# 1-Schematic_PIC18F_Breakout.net
KiCad netlist of a schematic drawn in EasyEDA
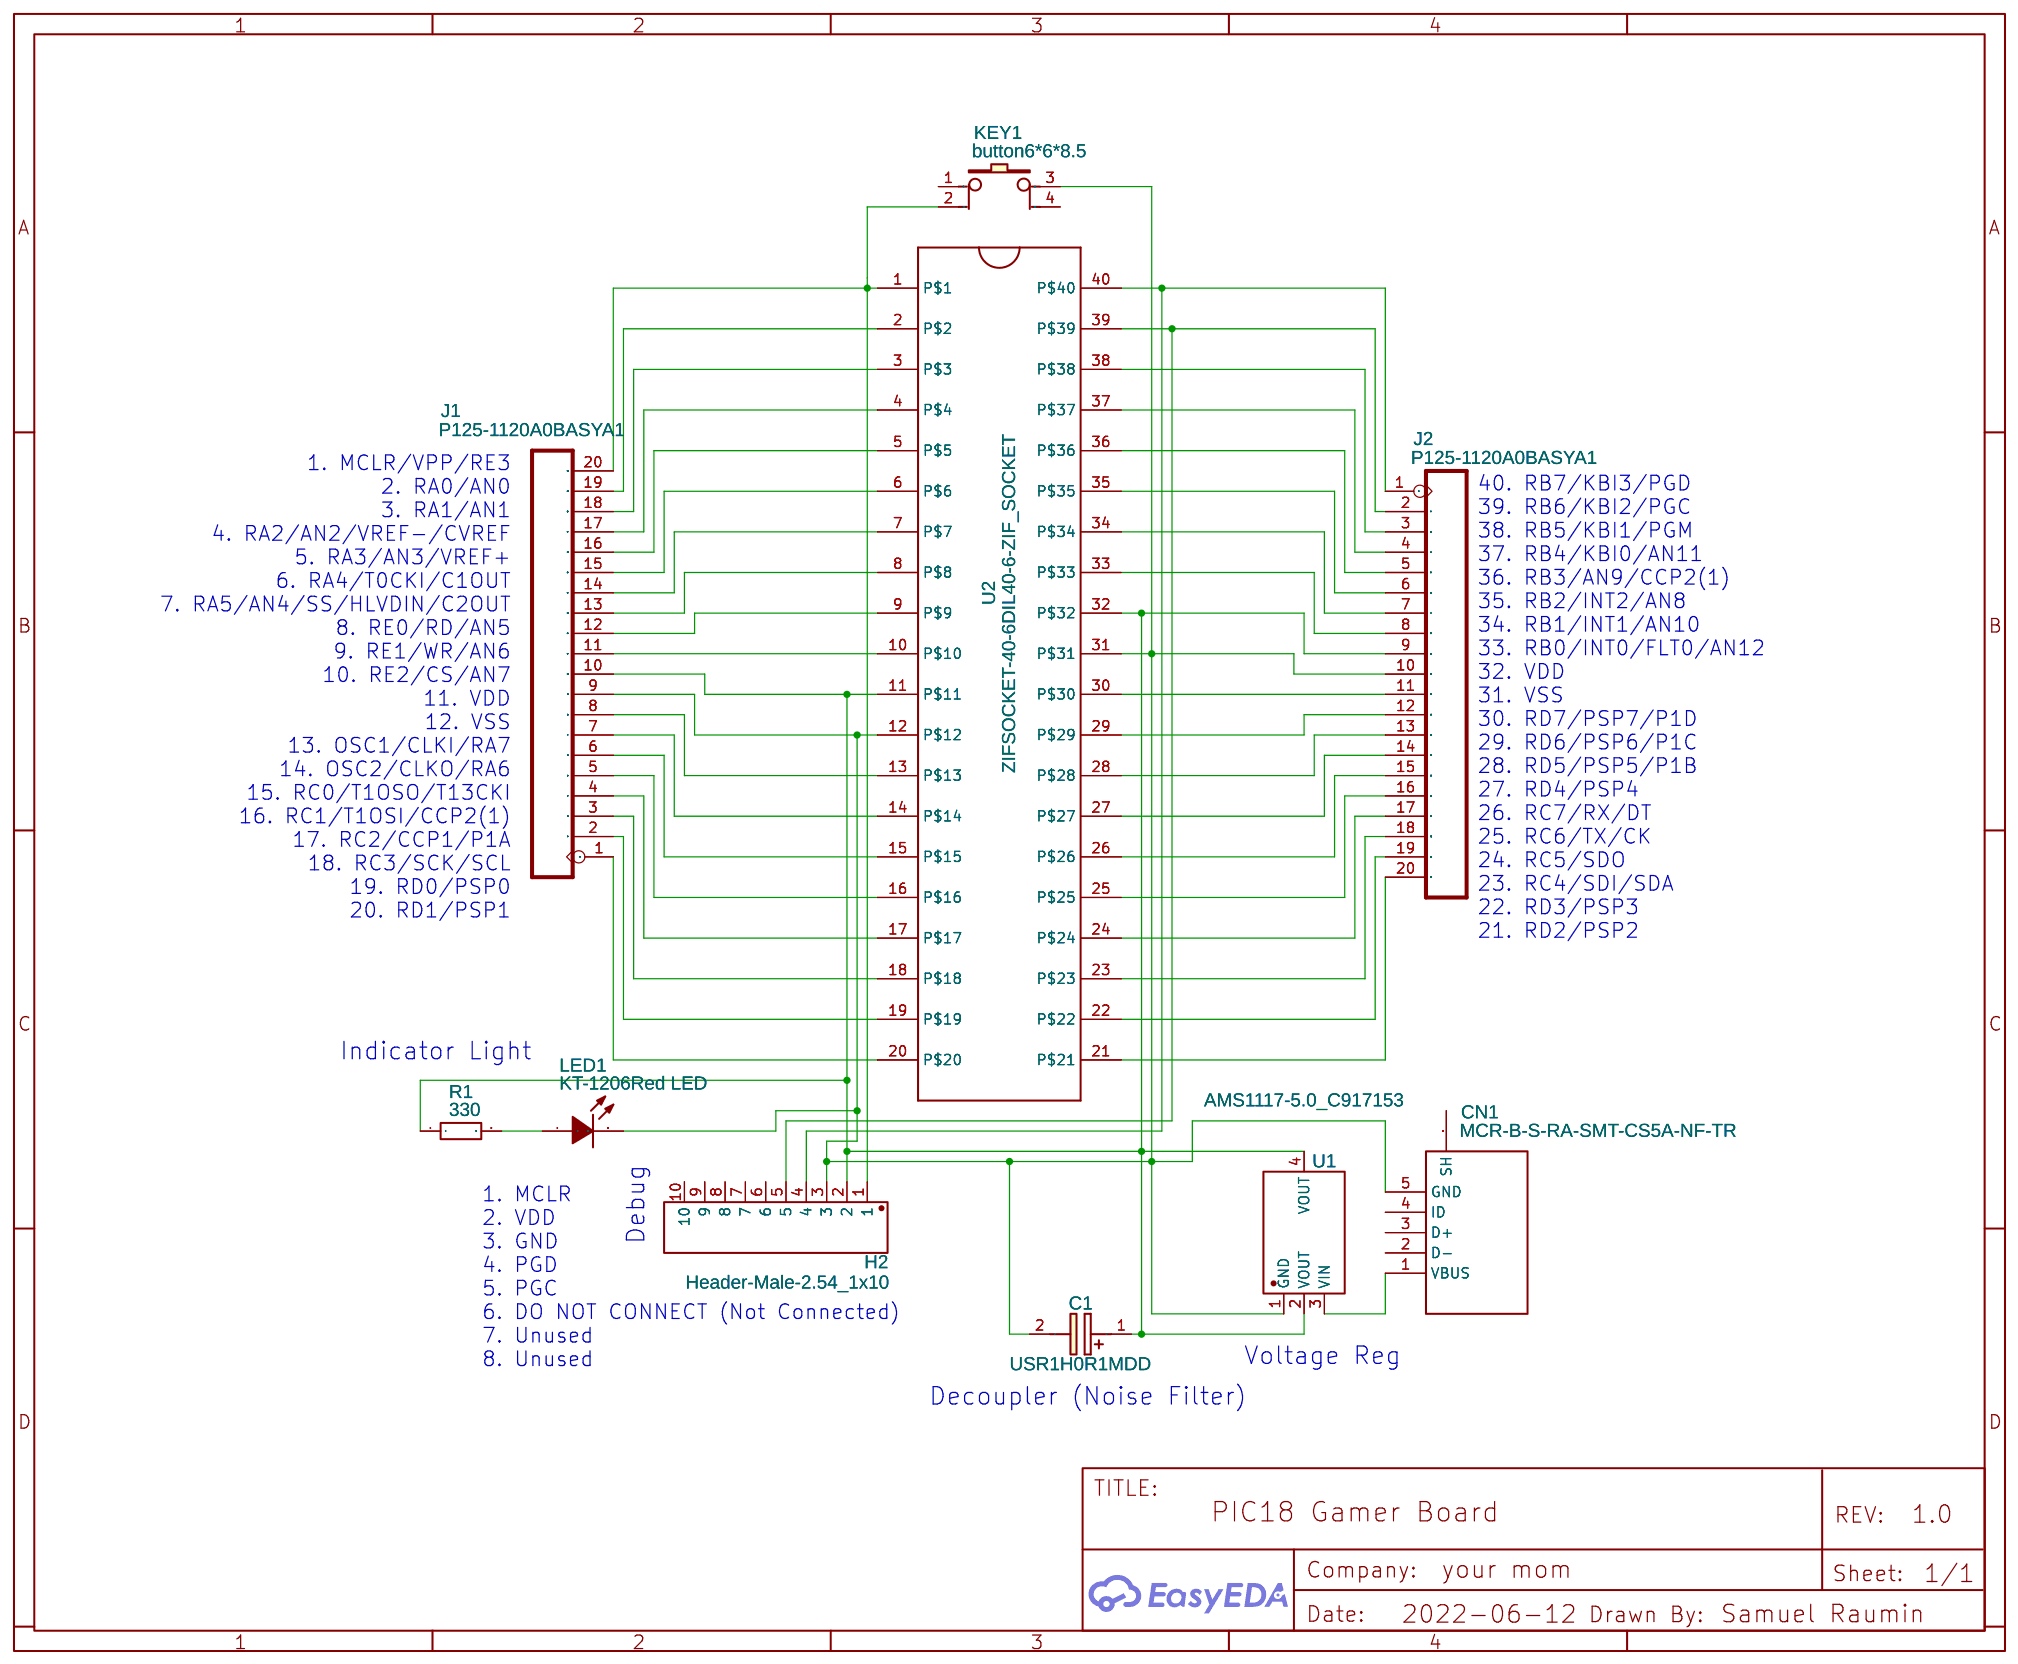
[diagram p0: schematic sheet]

(export (version "E")
  (design (tool "Eeschema 10.0.6"))
  (components
    (comp (ref "C1") (value "USR1H0R1MDD") (libsource (lib "") (part "USR1H0R1MDD")))
    (comp (ref "CN1")
      (value "MCR-B-S-RA-SMT-CS5A-NF-TR")
      (fields
        (field (name "BOM_Manufacturer Part") "MCR-B-S-RA-SMT-CS5A-NF-T/R")
        (field (name "BOM_Supplier Part") "2057-MCR-B-S-RA-SMT-CS5A-NF-T/R-ND")
      )
      (libsource (lib "") (part "MCR-B-S-RA-SMT-CS5A-NF-TR"))
    )
    (comp (ref "H2")
      (value "Header-Male-2.54_1x10")
      (fields
        (field (name "BOM_Manufacturer Part") "Headers  Pins2.54mm1*10P")
        (field (name "BOM_Supplier Part") "C57369")
      )
      (libsource (lib "") (part "Header-Male-2.54_1x10"))
    )
    (comp (ref "J1") (value "P125-1120A0BASYA1") (libsource (lib "") (part "P125-1120A0BASYA1_1")))
    (comp (ref "J2") (value "P125-1120A0BASYA1") (libsource (lib "") (part "P125-1120A0BASYA1")))
    (comp (ref "KEY1")
      (value "button6*6*8.5")
      (fields (field (name "BOM_Supplier Part") "C59980"))
      (libsource (lib "") (part "button6*6*8.5"))
    )
    (comp (ref "LED1")
      (value "KT-1206Red LED")
      (fields (field (name "BOM_Supplier Part") "C49018"))
      (libsource (lib "") (part "KT-1206Red LED"))
    )
    (comp (ref "R1")
      (value "330")
      (fields
        (field (name "BOM_Manufacturer Part") "AECR1206F5R10T9")
        (field (name "BOM_Supplier Part") "C352052")
      )
      (libsource (lib "") (part "AECR1206F5R10T9"))
    )
    (comp (ref "U1")
      (value "AMS1117-5.0_C917153")
      (fields
        (field (name "BOM_Manufacturer Part") "AMS1117-5.0")
        (field (name "BOM_Supplier Part") "C917153")
      )
      (libsource (lib "") (part "AMS1117-5.0_C917153"))
    )
    (comp (ref "U2")
      (value "ZIFSOCKET-40-6DIL40-6-ZIF_SOCKET")
      (libsource (lib "") (part "ZIFSOCKET-40-6DIL40-6-ZIF_SOCKET"))
    )
  )
  (nets
    (net (code "1") (name "Net-(C1-+)") (class "Default")
      (node (ref "C1") (pin "1") (pinfunction "+_1") (pintype "bidirectional"))
      (node (ref "H2") (pin "2") (pinfunction "2_2") (pintype "unspecified"))
      (node (ref "J1") (pin "10") (pinfunction "10_10") (pintype "unspecified"))
      (node (ref "J2") (pin "9") (pinfunction "9_9") (pintype "unspecified"))
      (node (ref "R1") (pin "1") (pinfunction "1_1") (pintype "unspecified"))
      (node (ref "U1") (pin "2") (pinfunction "VOUT_2") (pintype "unspecified"))
      (node (ref "U1") (pin "4") (pinfunction "VOUT_4") (pintype "unspecified"))
      (node (ref "U2") (pin "11") (pinfunction "P$11_11") (pintype "unspecified"))
      (node (ref "U2") (pin "32") (pinfunction "P$32_32") (pintype "unspecified"))
    )
    (net (code "2") (name "Net-(C1--)") (class "Default")
      (node (ref "C1") (pin "2") (pinfunction "-_2") (pintype "bidirectional"))
      (node (ref "CN1") (pin "5") (pinfunction "GND_5") (pintype "input"))
      (node (ref "H2") (pin "3") (pinfunction "3_3") (pintype "unspecified"))
      (node (ref "J1") (pin "9") (pinfunction "9_9") (pintype "unspecified"))
      (node (ref "J2") (pin "10") (pinfunction "10_10") (pintype "unspecified"))
      (node (ref "KEY1") (pin "3") (pinfunction "3_3") (pintype "input"))
      (node (ref "LED1") (pin "2") (pinfunction "K_2") (pintype "unspecified"))
      (node (ref "U1") (pin "1") (pinfunction "GND_1") (pintype "unspecified"))
      (node (ref "U2") (pin "12") (pinfunction "P$12_12") (pintype "unspecified"))
      (node (ref "U2") (pin "31") (pinfunction "P$31_31") (pintype "unspecified"))
    )
    (net (code "3") (name "Net-(CN1-VBUS)") (class "Default")
      (node (ref "CN1") (pin "1") (pinfunction "VBUS_1") (pintype "input"))
      (node (ref "U1") (pin "3") (pinfunction "VIN_3") (pintype "unspecified"))
    )
    (net (code "4") (name "Net-(LED1-A)") (class "Default")
      (node (ref "LED1") (pin "1") (pinfunction "A_1") (pintype "unspecified"))
      (node (ref "R1") (pin "2") (pinfunction "2_2") (pintype "unspecified"))
    )
    (net (code "5") (name "Net-(U2-P$1)") (class "Default")
      (node (ref "H2") (pin "1") (pinfunction "1_1") (pintype "unspecified"))
      (node (ref "J1") (pin "20") (pinfunction "20_20") (pintype "unspecified"))
      (node (ref "KEY1") (pin "2") (pinfunction "2_2") (pintype "input"))
      (node (ref "U2") (pin "1") (pinfunction "P$1_1") (pintype "unspecified"))
    )
    (net (code "6") (name "Net-(U2-P$2)") (class "Default")
      (node (ref "J1") (pin "19") (pinfunction "19_19") (pintype "unspecified"))
      (node (ref "U2") (pin "2") (pinfunction "P$2_2") (pintype "unspecified"))
    )
    (net (code "7") (name "Net-(U2-P$3)") (class "Default")
      (node (ref "J1") (pin "18") (pinfunction "18_18") (pintype "unspecified"))
      (node (ref "U2") (pin "3") (pinfunction "P$3_3") (pintype "unspecified"))
    )
    (net (code "8") (name "Net-(U2-P$4)") (class "Default")
      (node (ref "J1") (pin "17") (pinfunction "17_17") (pintype "unspecified"))
      (node (ref "U2") (pin "4") (pinfunction "P$4_4") (pintype "unspecified"))
    )
    (net (code "9") (name "Net-(U2-P$5)") (class "Default")
      (node (ref "J1") (pin "16") (pinfunction "16_16") (pintype "unspecified"))
      (node (ref "U2") (pin "5") (pinfunction "P$5_5") (pintype "unspecified"))
    )
    (net (code "10") (name "Net-(U2-P$6)") (class "Default")
      (node (ref "J1") (pin "15") (pinfunction "15_15") (pintype "unspecified"))
      (node (ref "U2") (pin "6") (pinfunction "P$6_6") (pintype "unspecified"))
    )
    (net (code "11") (name "Net-(U2-P$7)") (class "Default")
      (node (ref "J1") (pin "14") (pinfunction "14_14") (pintype "unspecified"))
      (node (ref "U2") (pin "7") (pinfunction "P$7_7") (pintype "unspecified"))
    )
    (net (code "12") (name "Net-(U2-P$8)") (class "Default")
      (node (ref "J1") (pin "13") (pinfunction "13_13") (pintype "unspecified"))
      (node (ref "U2") (pin "8") (pinfunction "P$8_8") (pintype "unspecified"))
    )
    (net (code "13") (name "Net-(U2-P$9)") (class "Default")
      (node (ref "J1") (pin "12") (pinfunction "12_12") (pintype "unspecified"))
      (node (ref "U2") (pin "9") (pinfunction "P$9_9") (pintype "unspecified"))
    )
    (net (code "14") (name "Net-(U2-P$10)") (class "Default")
      (node (ref "J1") (pin "11") (pinfunction "11_11") (pintype "unspecified"))
      (node (ref "U2") (pin "10") (pinfunction "P$10_10") (pintype "unspecified"))
    )
    (net (code "15") (name "Net-(U2-P$13)") (class "Default")
      (node (ref "J1") (pin "8") (pinfunction "8_8") (pintype "unspecified"))
      (node (ref "U2") (pin "13") (pinfunction "P$13_13") (pintype "unspecified"))
    )
    (net (code "16") (name "Net-(U2-P$14)") (class "Default")
      (node (ref "J1") (pin "7") (pinfunction "7_7") (pintype "unspecified"))
      (node (ref "U2") (pin "14") (pinfunction "P$14_14") (pintype "unspecified"))
    )
    (net (code "17") (name "Net-(U2-P$15)") (class "Default")
      (node (ref "J1") (pin "6") (pinfunction "6_6") (pintype "unspecified"))
      (node (ref "U2") (pin "15") (pinfunction "P$15_15") (pintype "unspecified"))
    )
    (net (code "18") (name "Net-(U2-P$16)") (class "Default")
      (node (ref "J1") (pin "5") (pinfunction "5_5") (pintype "unspecified"))
      (node (ref "U2") (pin "16") (pinfunction "P$16_16") (pintype "unspecified"))
    )
    (net (code "19") (name "Net-(U2-P$17)") (class "Default")
      (node (ref "J1") (pin "4") (pinfunction "4_4") (pintype "unspecified"))
      (node (ref "U2") (pin "17") (pinfunction "P$17_17") (pintype "unspecified"))
    )
    (net (code "20") (name "Net-(U2-P$18)") (class "Default")
      (node (ref "J1") (pin "3") (pinfunction "3_3") (pintype "unspecified"))
      (node (ref "U2") (pin "18") (pinfunction "P$18_18") (pintype "unspecified"))
    )
    (net (code "21") (name "Net-(U2-P$19)") (class "Default")
      (node (ref "J1") (pin "2") (pinfunction "2_2") (pintype "unspecified"))
      (node (ref "U2") (pin "19") (pinfunction "P$19_19") (pintype "unspecified"))
    )
    (net (code "22") (name "Net-(U2-P$20)") (class "Default")
      (node (ref "J1") (pin "1") (pinfunction "1_1") (pintype "unspecified"))
      (node (ref "U2") (pin "20") (pinfunction "P$20_20") (pintype "unspecified"))
    )
    (net (code "23") (name "Net-(U2-P$21)") (class "Default")
      (node (ref "J2") (pin "20") (pinfunction "20_20") (pintype "unspecified"))
      (node (ref "U2") (pin "21") (pinfunction "P$21_21") (pintype "unspecified"))
    )
    (net (code "24") (name "Net-(U2-P$22)") (class "Default")
      (node (ref "J2") (pin "19") (pinfunction "19_19") (pintype "unspecified"))
      (node (ref "U2") (pin "22") (pinfunction "P$22_22") (pintype "unspecified"))
    )
    (net (code "25") (name "Net-(U2-P$23)") (class "Default")
      (node (ref "J2") (pin "18") (pinfunction "18_18") (pintype "unspecified"))
      (node (ref "U2") (pin "23") (pinfunction "P$23_23") (pintype "unspecified"))
    )
    (net (code "26") (name "Net-(U2-P$24)") (class "Default")
      (node (ref "J2") (pin "17") (pinfunction "17_17") (pintype "unspecified"))
      (node (ref "U2") (pin "24") (pinfunction "P$24_24") (pintype "unspecified"))
    )
    (net (code "27") (name "Net-(U2-P$25)") (class "Default")
      (node (ref "J2") (pin "16") (pinfunction "16_16") (pintype "unspecified"))
      (node (ref "U2") (pin "25") (pinfunction "P$25_25") (pintype "unspecified"))
    )
    (net (code "28") (name "Net-(U2-P$26)") (class "Default")
      (node (ref "J2") (pin "15") (pinfunction "15_15") (pintype "unspecified"))
      (node (ref "U2") (pin "26") (pinfunction "P$26_26") (pintype "unspecified"))
    )
    (net (code "29") (name "Net-(U2-P$27)") (class "Default")
      (node (ref "J2") (pin "14") (pinfunction "14_14") (pintype "unspecified"))
      (node (ref "U2") (pin "27") (pinfunction "P$27_27") (pintype "unspecified"))
    )
    (net (code "30") (name "Net-(U2-P$28)") (class "Default")
      (node (ref "J2") (pin "13") (pinfunction "13_13") (pintype "unspecified"))
      (node (ref "U2") (pin "28") (pinfunction "P$28_28") (pintype "unspecified"))
    )
    (net (code "31") (name "Net-(U2-P$29)") (class "Default")
      (node (ref "J2") (pin "12") (pinfunction "12_12") (pintype "unspecified"))
      (node (ref "U2") (pin "29") (pinfunction "P$29_29") (pintype "unspecified"))
    )
    (net (code "32") (name "Net-(U2-P$30)") (class "Default")
      (node (ref "J2") (pin "11") (pinfunction "11_11") (pintype "unspecified"))
      (node (ref "U2") (pin "30") (pinfunction "P$30_30") (pintype "unspecified"))
    )
    (net (code "33") (name "Net-(U2-P$33)") (class "Default")
      (node (ref "J2") (pin "8") (pinfunction "8_8") (pintype "unspecified"))
      (node (ref "U2") (pin "33") (pinfunction "P$33_33") (pintype "unspecified"))
    )
    (net (code "34") (name "Net-(U2-P$34)") (class "Default")
      (node (ref "J2") (pin "7") (pinfunction "7_7") (pintype "unspecified"))
      (node (ref "U2") (pin "34") (pinfunction "P$34_34") (pintype "unspecified"))
    )
    (net (code "35") (name "Net-(U2-P$35)") (class "Default")
      (node (ref "J2") (pin "6") (pinfunction "6_6") (pintype "unspecified"))
      (node (ref "U2") (pin "35") (pinfunction "P$35_35") (pintype "unspecified"))
    )
    (net (code "36") (name "Net-(U2-P$36)") (class "Default")
      (node (ref "J2") (pin "5") (pinfunction "5_5") (pintype "unspecified"))
      (node (ref "U2") (pin "36") (pinfunction "P$36_36") (pintype "unspecified"))
    )
    (net (code "37") (name "Net-(U2-P$37)") (class "Default")
      (node (ref "J2") (pin "4") (pinfunction "4_4") (pintype "unspecified"))
      (node (ref "U2") (pin "37") (pinfunction "P$37_37") (pintype "unspecified"))
    )
    (net (code "38") (name "Net-(U2-P$38)") (class "Default")
      (node (ref "J2") (pin "3") (pinfunction "3_3") (pintype "unspecified"))
      (node (ref "U2") (pin "38") (pinfunction "P$38_38") (pintype "unspecified"))
    )
    (net (code "39") (name "Net-(U2-P$39)") (class "Default")
      (node (ref "H2") (pin "5") (pinfunction "5_5") (pintype "unspecified"))
      (node (ref "J2") (pin "2") (pinfunction "2_2") (pintype "unspecified"))
      (node (ref "U2") (pin "39") (pinfunction "P$39_39") (pintype "unspecified"))
    )
    (net (code "40") (name "Net-(U2-P$40)") (class "Default")
      (node (ref "H2") (pin "4") (pinfunction "4_4") (pintype "unspecified"))
      (node (ref "J2") (pin "1") (pinfunction "1_1") (pintype "unspecified"))
      (node (ref "U2") (pin "40") (pinfunction "P$40_40") (pintype "unspecified"))
    )
    (net (code "41") (name "unconnected-(CN1-D+-Pad3)") (class "Default")
      (node (ref "CN1") (pin "3") (pinfunction "D+_3") (pintype "input"))
    )
    (net (code "42") (name "unconnected-(CN1-D--Pad2)") (class "Default")
      (node (ref "CN1") (pin "2") (pinfunction "D-_2") (pintype "input"))
    )
    (net (code "43") (name "unconnected-(CN1-ID-Pad4)") (class "Default")
      (node (ref "CN1") (pin "4") (pinfunction "ID_4") (pintype "input"))
    )
    (net (code "44") (name "unconnected-(CN1-SH-Pad0)") (class "Default")
      (node (ref "CN1") (pin "0") (pinfunction "SH_0") (pintype "input"))
    )
    (net (code "45") (name "unconnected-(H2-Pad6)") (class "Default")
      (node (ref "H2") (pin "6") (pinfunction "6_6") (pintype "unspecified"))
    )
    (net (code "46") (name "unconnected-(H2-Pad7)") (class "Default")
      (node (ref "H2") (pin "7") (pinfunction "7_7") (pintype "unspecified"))
    )
    (net (code "47") (name "unconnected-(H2-Pad8)") (class "Default")
      (node (ref "H2") (pin "8") (pinfunction "8_8") (pintype "unspecified"))
    )
    (net (code "48") (name "unconnected-(H2-Pad9)") (class "Default")
      (node (ref "H2") (pin "9") (pinfunction "9_9") (pintype "unspecified"))
    )
    (net (code "49") (name "unconnected-(H2-Pad10)") (class "Default")
      (node (ref "H2") (pin "10") (pinfunction "10_10") (pintype "unspecified"))
    )
    (net (code "50") (name "unconnected-(KEY1-Pad1)") (class "Default")
      (node (ref "KEY1") (pin "1") (pinfunction "1_1") (pintype "input"))
    )
    (net (code "51") (name "unconnected-(KEY1-Pad4)") (class "Default")
      (node (ref "KEY1") (pin "4") (pinfunction "4_4") (pintype "input"))
    )
  )
)
